# CFD_V1_03_Main.net
KiCad netlist of a schematic drawn in Altium Designer
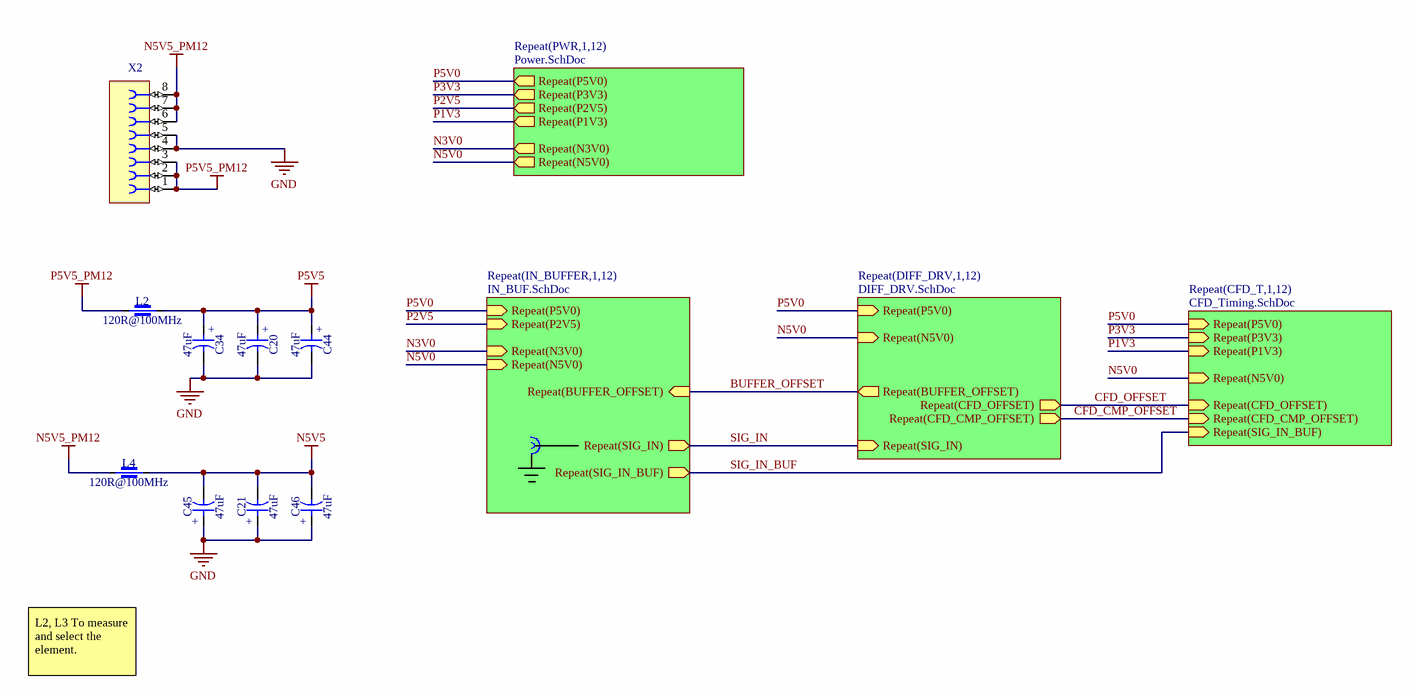
[diagram p0: CFD_V1.03_Main.SchDoc]

(export (version "E")
  (design (tool "Eeschema 10.0.6"))
  (components
    (comp (ref "C20")
      (value "47uF")
      (footprint "CAPAE530X610N")
      (description "Polarised capacitor")
      (fields
        (field (name "PART NUMBER") "CAE530-610_47UF_16V_20%")
        (field (name "VOLTAGE") "16V")
        (field (name "AUTHOR") "CERN DEM HF")
      )
      (libsource (lib "Capacitors") (part "Capacitor - polarized"))
    )
    (comp (ref "C21")
      (value "47uF")
      (footprint "CAPAE530X610N")
      (description "Polarised capacitor")
      (fields
        (field (name "PART NUMBER") "CAE530-610_47UF_16V_20%")
        (field (name "VOLTAGE") "16V")
        (field (name "AUTHOR") "CERN DEM HF")
      )
      (libsource (lib "Capacitors") (part "Capacitor - polarized"))
    )
    (comp (ref "C34")
      (value "47uF")
      (footprint "CAPAE530X610N")
      (description "Polarised capacitor")
      (fields
        (field (name "PART NUMBER") "CAE530-610_47UF_16V_20%")
        (field (name "VOLTAGE") "16V")
        (field (name "AUTHOR") "CERN DEM HF")
      )
      (libsource (lib "Capacitors") (part "Capacitor - polarized"))
    )
    (comp (ref "C44")
      (value "47uF")
      (footprint "CAPAE530X610N")
      (description "Polarised capacitor")
      (fields
        (field (name "PART NUMBER") "CAE530-610_47UF_16V_20%")
        (field (name "VOLTAGE") "16V")
        (field (name "AUTHOR") "CERN DEM HF")
      )
      (libsource (lib "Capacitors") (part "Capacitor - polarized"))
    )
    (comp (ref "C45")
      (value "47uF")
      (footprint "CAPAE530X610N")
      (description "Polarised capacitor")
      (fields
        (field (name "PART NUMBER") "CAE530-610_47UF_16V_20%")
        (field (name "VOLTAGE") "16V")
        (field (name "AUTHOR") "CERN DEM HF")
      )
      (libsource (lib "Capacitors") (part "Capacitor - polarized"))
    )
    (comp (ref "C46")
      (value "47uF")
      (footprint "CAPAE530X610N")
      (description "Polarised capacitor")
      (fields
        (field (name "PART NUMBER") "CAE530-610_47UF_16V_20%")
        (field (name "VOLTAGE") "16V")
        (field (name "AUTHOR") "CERN DEM HF")
      )
      (libsource (lib "Capacitors") (part "Capacitor - polarized"))
    )
    (comp (ref "L2")
      (value "120R@100MHz")
      (footprint "IND_MURATA_BLM31KN")
      (fields
        (field (name "PART NUMBER") "IND1206_MURATA_BLM31KN121SN1")
        (field (name "POWER") "6A")
        (field (name "TOLERANCE") "±25%")
        (field (name "AUTHOR") "CERN DEM HF")
      )
      (libsource (lib "Inductors & Transformers") (part "Ferrite Bead"))
    )
    (comp (ref "L4")
      (value "120R@100MHz")
      (footprint "IND_MURATA_BLM31KN")
      (fields
        (field (name "PART NUMBER") "IND1206_MURATA_BLM31KN121SN1")
        (field (name "POWER") "6A")
        (field (name "TOLERANCE") "±25%")
        (field (name "AUTHOR") "CERN DEM HF")
      )
      (libsource (lib "Inductors & Transformers") (part "Ferrite Bead"))
    )
    (comp (ref "X2")
      (value "Socket 8")
      (footprint "SAMTEC_CES-108-01-T-S")
      (description "Connector 8 Female")
      (fields
        (field (name "PART NUMBER") "SAMTEC_CES-108-01-L-S")
        (field (name "MANUFACTURER") "SAMTEC")
        (field (name "AUTHOR") "CERN DEM HF")
      )
      (libsource (lib "Connectors") (part "Connector 8 Female"))
    )
  )
  (nets
    (net (code "12") (name "GND") (class "Default")
      (node (ref "C20") (pin "2") (pinfunction "2_2") (pintype "passive"))
      (node (ref "C21") (pin "1") (pinfunction "1_1") (pintype "passive"))
      (node (ref "C34") (pin "2") (pinfunction "2_2") (pintype "passive"))
      (node (ref "C44") (pin "2") (pinfunction "2_2") (pintype "passive"))
      (node (ref "C45") (pin "1") (pinfunction "1_1") (pintype "passive"))
      (node (ref "C46") (pin "1") (pinfunction "1_1") (pintype "passive"))
      (node (ref "X2") (pin "4") (pinfunction "4_4") (pintype "bidirectional"))
      (node (ref "X2") (pin "5") (pinfunction "5_5") (pintype "bidirectional"))
    )
    (net (code "13") (name "N5V5") (class "Default")
      (node (ref "C21") (pin "2") (pinfunction "2_2") (pintype "passive"))
      (node (ref "C45") (pin "2") (pinfunction "2_2") (pintype "passive"))
      (node (ref "C46") (pin "2") (pinfunction "2_2") (pintype "passive"))
      (node (ref "L4") (pin "2") (pinfunction "2_2") (pintype "passive"))
    )
    (net (code "14") (name "N5V5_PM12") (class "Default")
      (node (ref "L4") (pin "1") (pinfunction "1_1") (pintype "passive"))
      (node (ref "X2") (pin "6") (pinfunction "6_6") (pintype "bidirectional"))
      (node (ref "X2") (pin "7") (pinfunction "7_7") (pintype "bidirectional"))
      (node (ref "X2") (pin "8") (pinfunction "8_8") (pintype "bidirectional"))
    )
    (net (code "15") (name "P5V5") (class "Default")
      (node (ref "C20") (pin "1") (pinfunction "1_1") (pintype "passive"))
      (node (ref "C34") (pin "1") (pinfunction "1_1") (pintype "passive"))
      (node (ref "C44") (pin "1") (pinfunction "1_1") (pintype "passive"))
      (node (ref "L2") (pin "2") (pinfunction "2_2") (pintype "passive"))
    )
    (net (code "16") (name "P5V5_PM12") (class "Default")
      (node (ref "L2") (pin "1") (pinfunction "1_1") (pintype "passive"))
      (node (ref "X2") (pin "1") (pinfunction "1_1") (pintype "bidirectional"))
      (node (ref "X2") (pin "2") (pinfunction "2_2") (pintype "bidirectional"))
      (node (ref "X2") (pin "3") (pinfunction "3_3") (pintype "bidirectional"))
    )
  )
)
